# Main.net
KiCad netlist of a schematic drawn in Altium Designer
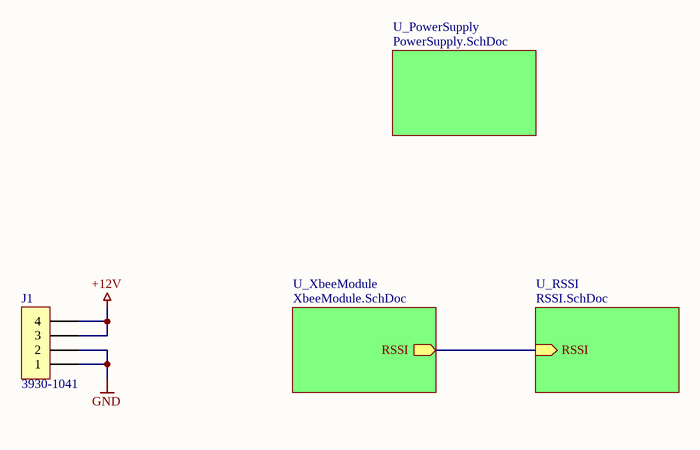
[diagram p0: Main.SchDoc]

(export (version "E")
  (design (tool "Eeschema 10.0.6"))
  (components
    (comp (ref "J1")
      (value "3930-1041")
      (footprint "MOLEX-3930-1041")
      (description "Molex MiniFit, Dual Row, Right Angle 3930-1041")
      (libsource (lib "Alt") (part "Molex-MiniFit-4-RA"))
    )
  )
  (nets
    (net (code "1") (name "+12V") (class "Default")
      (node (ref "J1") (pin "3") (pinfunction "3_3") (pintype "power_in"))
      (node (ref "J1") (pin "4") (pinfunction "4_4") (pintype "power_in"))
    )
    (net (code "3") (name "GND") (class "Default")
      (node (ref "J1") (pin "1") (pinfunction "1_1") (pintype "power_in"))
      (node (ref "J1") (pin "2") (pinfunction "2_2") (pintype "power_in"))
    )
  )
)
